# FINAL_VERSION.net
KiCad netlist of a schematic drawn in Altium Designer
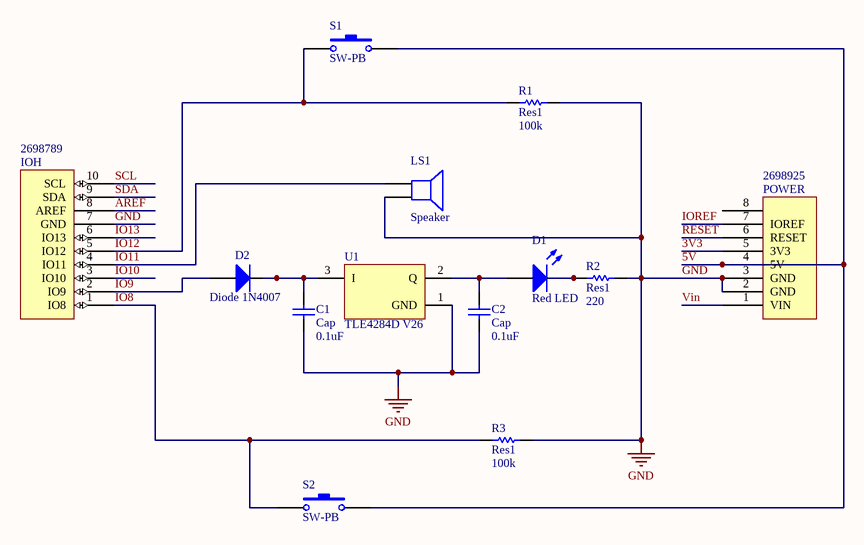
[diagram p0: FINAL VERSION.SchDoc]

(export (version "E")
  (design (tool "Eeschema 10.0.6"))
  (components
    (comp (ref "C1")
      (value "Cap")
      (footprint "RAD-0.3")
      (description "Capacitor")
      (fields (field (name "ALTIUM_VALUE") "0.1uF") (field (name "PUBLISHER") "Altium Limited"))
      (libsource (lib "Miscellaneous Devices") (part "Cap"))
    )
    (comp (ref "C2")
      (value "Cap")
      (footprint "RAD-0.3")
      (description "Capacitor")
      (fields (field (name "ALTIUM_VALUE") "0.1uF") (field (name "PUBLISHER") "Altium Limited"))
      (libsource (lib "Miscellaneous Devices") (part "Cap"))
    )
    (comp (ref "D1")
      (value "Red LED")
      (footprint "3.2X1.6X1.1")
      (description "Typical RED, GREEN, YELLOW, AMBER GaAs LED")
      (fields (field (name "PUBLISHER") "Altium Limited"))
      (libsource (lib "Miscellaneous Devices") (part "LED2"))
    )
    (comp (ref "D2")
      (value "Diode 1N4007")
      (footprint "DO-41")
      (description "1 Amp General Purpose Rectifier")
      (fields (field (name "PUBLISHER") "Altium Limited"))
      (libsource (lib "Miscellaneous Devices") (part "Diode 1N4007"))
    )
    (comp (ref "IOH")
      (value "IOH")
      (footprint "Header:Header 10x1 8.5mm")
      (fields (field (name "SUPPLIER PART NUMBER 3") "2698789"))
      (libsource (lib "Header") (part "IOH"))
    )
    (comp (ref "LS1")
      (value "Speaker")
      (footprint "PIN2")
      (description "Loudspeaker")
      (fields (field (name "PUBLISHER") "Altium Limited"))
      (libsource (lib "Miscellaneous Devices") (part "Speaker"))
    )
    (comp (ref "POWER")
      (value "POWER_UNO")
      (footprint "Header 8x1 8.5mm")
      (fields (field (name "SUPPLIER PART NUMBER 4") "2698925"))
      (libsource (lib "Header") (part "POWER_UNO"))
    )
    (comp (ref "R1")
      (value "Res1")
      (footprint "AXIAL-0.3")
      (description "Resistor")
      (fields (field (name "ALTIUM_VALUE") "100k") (field (name "PUBLISHER") "Altium Limited"))
      (libsource (lib "Miscellaneous Devices") (part "Res1"))
    )
    (comp (ref "R2")
      (value "Res1")
      (footprint "AXIAL-0.3")
      (description "Resistor")
      (fields (field (name "ALTIUM_VALUE") "220") (field (name "PUBLISHER") "Altium Limited"))
      (libsource (lib "Miscellaneous Devices") (part "Res1"))
    )
    (comp (ref "R3")
      (value "Res1")
      (footprint "AXIAL-0.3")
      (description "Resistor")
      (fields (field (name "ALTIUM_VALUE") "100k") (field (name "PUBLISHER") "Altium Limited"))
      (libsource (lib "Miscellaneous Devices") (part "Res1"))
    )
    (comp (ref "S1")
      (value "SW-PB")
      (footprint "SPST-2")
      (description "Switch")
      (fields (field (name "PUBLISHER") "Altium Limited"))
      (libsource (lib "Miscellaneous Devices") (part "SW-PB"))
    )
    (comp (ref "S2")
      (value "SW-PB")
      (footprint "SPST-2")
      (description "Switch")
      (fields (field (name "PUBLISHER") "Altium Limited"))
      (libsource (lib "Miscellaneous Devices") (part "SW-PB"))
    )
    (comp (ref "U1")
      (value "TLE4284D V26")
      (footprint "INF-PG-TO252-3-11_N")
      (description "Voltage Regulator, 4 to 40 V Supply, 2.6 V Output, -40 to 150 degC, PG-TO252-3-11, Reel, Green")
      (fields (field (name "MANUFACTURER") "Infineon"))
      (libsource (lib "Infineon_Power_Supply_Voltage_Regulator") (part "TLE4284D V26"))
    )
  )
  (nets
    (net (code "1") (name "/3V3") (class "Default")
      (node (ref "POWER") (pin "5") (pinfunction "3V3_5") (pintype "power_in"))
    )
    (net (code "2") (name "/5V") (class "Default")
      (node (ref "POWER") (pin "4") (pinfunction "5V_4") (pintype "power_in"))
      (node (ref "S1") (pin "2") (pinfunction "2_2") (pintype "passive"))
      (node (ref "S2") (pin "2") (pinfunction "2_2") (pintype "passive"))
    )
    (net (code "4") (name "/AREF") (class "Default")
      (node (ref "IOH") (pin "8") (pinfunction "AREF_8") (pintype "passive"))
    )
    (net (code "5") (name "/IO8") (class "Default")
      (node (ref "IOH") (pin "1") (pinfunction "IO8_1") (pintype "bidirectional"))
      (node (ref "R3") (pin "1") (pinfunction "1_1") (pintype "passive"))
      (node (ref "S2") (pin "1") (pinfunction "1_1") (pintype "passive"))
    )
    (net (code "6") (name "/IO9") (class "Default")
      (node (ref "D2") (pin "1") (pinfunction "A_1") (pintype "passive"))
      (node (ref "IOH") (pin "2") (pinfunction "IO9_2") (pintype "bidirectional"))
    )
    (net (code "7") (name "/IO10") (class "Default")
      (node (ref "IOH") (pin "3") (pinfunction "IO10_3") (pintype "bidirectional"))
    )
    (net (code "8") (name "/IO11") (class "Default")
      (node (ref "IOH") (pin "4") (pinfunction "IO11_4") (pintype "bidirectional"))
      (node (ref "LS1") (pin "1") (pinfunction "1_1") (pintype "passive"))
    )
    (net (code "9") (name "/IO12") (class "Default")
      (node (ref "IOH") (pin "5") (pinfunction "IO12_5") (pintype "bidirectional"))
      (node (ref "R1") (pin "1") (pinfunction "1_1") (pintype "passive"))
      (node (ref "S1") (pin "1") (pinfunction "1_1") (pintype "passive"))
    )
    (net (code "10") (name "/IO13") (class "Default")
      (node (ref "IOH") (pin "6") (pinfunction "IO13_6") (pintype "bidirectional"))
    )
    (net (code "11") (name "/IOREF") (class "Default")
      (node (ref "POWER") (pin "7") (pinfunction "IOREF_7") (pintype "power_in"))
    )
    (net (code "12") (name "/RESET") (class "Default")
      (node (ref "POWER") (pin "6") (pinfunction "RESET_6") (pintype "passive"))
    )
    (net (code "13") (name "/SCL") (class "Default")
      (node (ref "IOH") (pin "10") (pinfunction "SCL_10") (pintype "bidirectional"))
    )
    (net (code "14") (name "/SDA") (class "Default")
      (node (ref "IOH") (pin "9") (pinfunction "SDA_9") (pintype "bidirectional"))
    )
    (net (code "15") (name "/Vin") (class "Default")
      (node (ref "POWER") (pin "1") (pinfunction "VIN_1") (pintype "power_in"))
    )
    (net (code "16") (name "GND") (class "Default")
      (node (ref "C1") (pin "1") (pinfunction "1_1") (pintype "passive"))
      (node (ref "C2") (pin "1") (pinfunction "1_1") (pintype "passive"))
      (node (ref "IOH") (pin "7") (pinfunction "GND_7") (pintype "power_in"))
      (node (ref "LS1") (pin "2") (pinfunction "2_2") (pintype "passive"))
      (node (ref "POWER") (pin "2") (pinfunction "GND_2") (pintype "power_in"))
      (node (ref "POWER") (pin "3") (pinfunction "GND_3") (pintype "power_in"))
      (node (ref "R1") (pin "2") (pinfunction "2_2") (pintype "passive"))
      (node (ref "R2") (pin "2") (pinfunction "2_2") (pintype "passive"))
      (node (ref "R3") (pin "2") (pinfunction "2_2") (pintype "passive"))
      (node (ref "U1") (pin "1") (pinfunction "GND_1") (pintype "power_in"))
    )
    (net (code "17") (name "Net-(D1-A)") (class "Default")
      (node (ref "C2") (pin "2") (pinfunction "2_2") (pintype "passive"))
      (node (ref "D1") (pin "1") (pinfunction "A_1") (pintype "passive"))
      (node (ref "U1") (pin "2") (pinfunction "Q_2") (pintype "power_in"))
    )
    (net (code "18") (name "Net-(D1-K)") (class "Default")
      (node (ref "D1") (pin "2") (pinfunction "K_2") (pintype "passive"))
      (node (ref "R2") (pin "1") (pinfunction "1_1") (pintype "passive"))
    )
    (net (code "19") (name "Net-(D2-K)") (class "Default")
      (node (ref "C1") (pin "2") (pinfunction "2_2") (pintype "passive"))
      (node (ref "D2") (pin "2") (pinfunction "K_2") (pintype "passive"))
      (node (ref "U1") (pin "3") (pinfunction "I_3") (pintype "power_in"))
    )
    (net (code "20") (name "unconnected-(POWER-Pad8)") (class "Default")
      (node (ref "POWER") (pin "8") (pintype "passive"))
    )
  )
)
